# Sheet1.net
KiCad netlist of a schematic drawn in Altium Designer
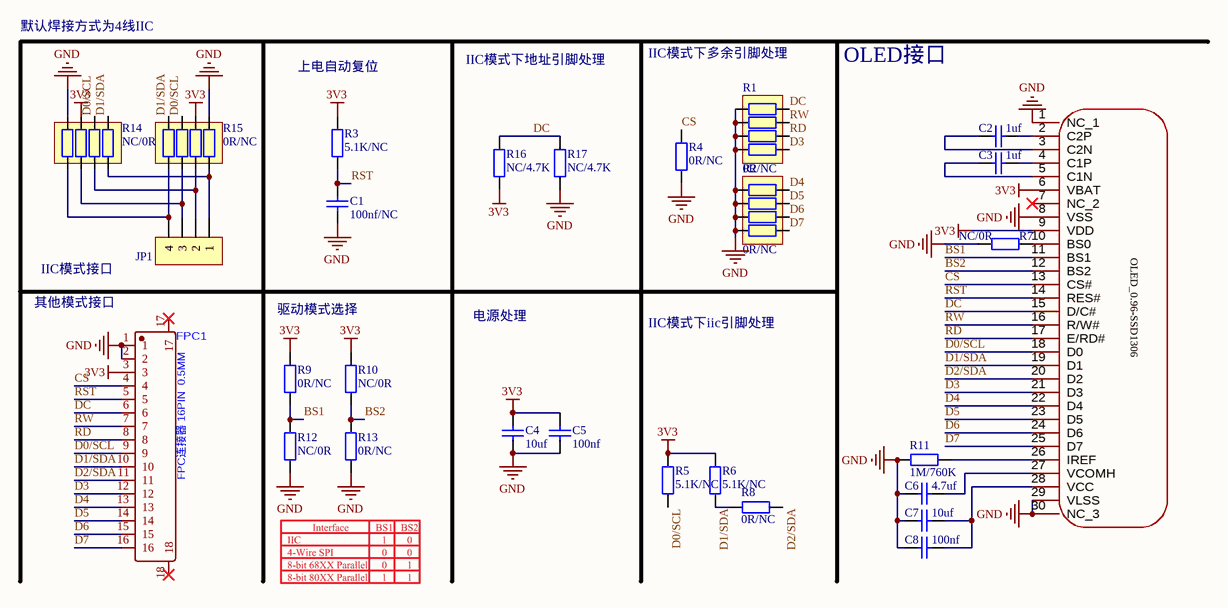
[diagram p0: Sheet1.SchDoc]

(export (version "E")
  (design (tool "Eeschema 10.0.6"))
  (components
    (comp (ref "C1")
      (value "100nf/NC")
      (footprint "PCB1:C0402_L")
      (description "贴片电容/MLCC电容")
      (libsource (lib "0.96_OLED_screen") (part "C"))
    )
    (comp (ref "C2")
      (value "1uf")
      (footprint "PCB1:C0402_L")
      (description "贴片电容/MLCC电容")
      (libsource (lib "0.96_OLED_screen") (part "C"))
    )
    (comp (ref "C3")
      (value "1uf")
      (footprint "PCB1:C0402_L")
      (description "贴片电容/MLCC电容")
      (libsource (lib "0.96_OLED_screen") (part "C"))
    )
    (comp (ref "C4")
      (value "10uf")
      (footprint "PCB1:C0402_L")
      (description "贴片电容/MLCC电容")
      (libsource (lib "0.96_OLED_screen") (part "C"))
    )
    (comp (ref "C5")
      (value "100nf")
      (footprint "PCB1:C0402_L")
      (description "贴片电容/MLCC电容")
      (libsource (lib "0.96_OLED_screen") (part "C"))
    )
    (comp (ref "C6")
      (value "4.7uf")
      (footprint "PCB1:C0402_L")
      (description "贴片电容/MLCC电容")
      (libsource (lib "0.96_OLED_screen") (part "C"))
    )
    (comp (ref "C7")
      (value "10uf")
      (footprint "PCB1:C0402_L")
      (description "贴片电容/MLCC电容")
      (libsource (lib "0.96_OLED_screen") (part "C"))
    )
    (comp (ref "C8")
      (value "100nf")
      (footprint "PCB1:C0402_L")
      (description "贴片电容/MLCC电容")
      (libsource (lib "0.96_OLED_screen") (part "C"))
    )
    (comp (ref "FPC1")
      (value "FPC连接器 16PIN  0.5MM")
      (footprint "PCB1:FPC-SMD_FPC-0.5MM-16P")
      (libsource (lib "0.96_OLED_screen") (part "FPC连接器 16PIN  0.5MM"))
    )
    (comp (ref "JP1")
      (value "HDR-1X4")
      (footprint "PCB1:HDR2.54-LI-4P")
      (description "4P接插件")
      (libsource (lib "0.96_OLED_screen") (part "Header 4"))
    )
    (comp (ref "R1")
      (value "0R/NC")
      (footprint "PCB1:RCA-8P4R-0402")
      (description "贴片4P排阻")
      (libsource (lib "") (part "R-8P4R_1"))
    )
    (comp (ref "R2")
      (value "0R/NC")
      (footprint "PCB1:RCA-8P4R-0402")
      (description "贴片4P排阻")
      (libsource (lib "") (part "R-8P4R_1"))
    )
    (comp (ref "R3")
      (value "5.1K/NC")
      (footprint "PCB1:R0402_L")
      (description "贴片电阻")
      (libsource (lib "0.96_OLED_screen") (part "R"))
    )
    (comp (ref "R4")
      (value "0R/NC")
      (footprint "PCB1:R0402_L")
      (description "贴片电阻")
      (libsource (lib "0.96_OLED_screen") (part "R"))
    )
    (comp (ref "R5")
      (value "5.1K/NC")
      (footprint "PCB1:R0402_L")
      (description "贴片电阻")
      (libsource (lib "0.96_OLED_screen") (part "R"))
    )
    (comp (ref "R6")
      (value "5.1K/NC")
      (footprint "PCB1:R0402_L")
      (description "贴片电阻")
      (libsource (lib "0.96_OLED_screen") (part "R"))
    )
    (comp (ref "R7")
      (value "NC/0R")
      (footprint "PCB1:R0402_L")
      (description "贴片电阻")
      (libsource (lib "0.96_OLED_screen") (part "R"))
    )
    (comp (ref "R8")
      (value "0R/NC")
      (footprint "PCB1:R0402_L")
      (description "贴片电阻")
      (libsource (lib "0.96_OLED_screen") (part "R"))
    )
    (comp (ref "R9")
      (value "0R/NC")
      (footprint "PCB1:R0402_L")
      (description "贴片电阻")
      (libsource (lib "0.96_OLED_screen") (part "R"))
    )
    (comp (ref "R10")
      (value "NC/0R")
      (footprint "PCB1:R0402_L")
      (description "贴片电阻")
      (libsource (lib "0.96_OLED_screen") (part "R"))
    )
    (comp (ref "R11")
      (value "1M/760K")
      (footprint "PCB1:R0402_L")
      (description "贴片电阻")
      (libsource (lib "0.96_OLED_screen") (part "R"))
    )
    (comp (ref "R12")
      (value "NC/0R")
      (footprint "PCB1:R0402_L")
      (description "贴片电阻")
      (libsource (lib "0.96_OLED_screen") (part "R"))
    )
    (comp (ref "R13")
      (value "0R/NC")
      (footprint "PCB1:R0402_L")
      (description "贴片电阻")
      (libsource (lib "0.96_OLED_screen") (part "R"))
    )
    (comp (ref "R14")
      (value "NC/0R")
      (footprint "PCB1:RCA-8P4R-0402")
      (description "贴片电阻")
      (libsource (lib "0.96_OLED_screen") (part "R-8P4R"))
    )
    (comp (ref "R15")
      (value "0R/NC")
      (footprint "PCB1:RCA-8P4R-0402")
      (description "贴片4P排阻")
      (libsource (lib "0.96_OLED_screen") (part "R-8P4R"))
    )
    (comp (ref "R16")
      (value "NC/4.7K")
      (footprint "PCB1:R0402_L")
      (description "贴片电阻")
      (libsource (lib "0.96_OLED_screen") (part "R"))
    )
    (comp (ref "R17")
      (value "NC/4.7K")
      (footprint "PCB1:R0402_L")
      (description "贴片电阻")
      (libsource (lib "0.96_OLED_screen") (part "R"))
    )
    (comp (ref "U1")
      (value "SSD1306")
      (footprint "PCB1:1.3OLED-2")
      (libsource (lib "0.96_OLED_screen") (part "SSD1306"))
    )
  )
  (nets
    (net (code "1") (name "/BS1") (class "Default")
      (node (ref "R12") (pin "2") (pinfunction "2_2") (pintype "passive"))
      (node (ref "R9") (pin "1") (pinfunction "1_1") (pintype "passive"))
      (node (ref "U1") (pin "11") (pinfunction "BS1_11") (pintype "passive"))
    )
    (net (code "2") (name "/BS2") (class "Default")
      (node (ref "R10") (pin "1") (pinfunction "1_1") (pintype "passive"))
      (node (ref "R13") (pin "2") (pinfunction "2_2") (pintype "passive"))
      (node (ref "U1") (pin "12") (pinfunction "BS2_12") (pintype "passive"))
    )
    (net (code "3") (name "/CS") (class "Default")
      (node (ref "FPC1") (pin "4") (pinfunction "4_4") (pintype "passive"))
      (node (ref "R4") (pin "1") (pinfunction "1_1") (pintype "passive"))
      (node (ref "U1") (pin "13") (pinfunction "CS#_13") (pintype "passive"))
    )
    (net (code "4") (name "/D0{slash}SCL") (class "Default")
      (node (ref "FPC1") (pin "9") (pinfunction "9_9") (pintype "passive"))
      (node (ref "R14") (pin "6") (pinfunction "6_6") (pintype "passive"))
      (node (ref "R15") (pin "7") (pinfunction "7_7") (pintype "passive"))
      (node (ref "R5") (pin "1") (pinfunction "1_1") (pintype "passive"))
      (node (ref "U1") (pin "18") (pinfunction "D0_18") (pintype "passive"))
    )
    (net (code "5") (name "/D1{slash}SDA") (class "Default")
      (node (ref "FPC1") (pin "10") (pinfunction "10_10") (pintype "passive"))
      (node (ref "R14") (pin "5") (pinfunction "5_5") (pintype "passive"))
      (node (ref "R15") (pin "8") (pinfunction "8_8") (pintype "passive"))
      (node (ref "R6") (pin "1") (pinfunction "1_1") (pintype "passive"))
      (node (ref "R8") (pin "2") (pinfunction "2_2") (pintype "passive"))
      (node (ref "U1") (pin "19") (pinfunction "D1_19") (pintype "passive"))
    )
    (net (code "6") (name "/D2{slash}SDA") (class "Default")
      (node (ref "FPC1") (pin "11") (pinfunction "11_11") (pintype "passive"))
      (node (ref "R8") (pin "1") (pinfunction "1_1") (pintype "passive"))
      (node (ref "U1") (pin "20") (pinfunction "D2_20") (pintype "passive"))
    )
    (net (code "7") (name "/D3") (class "Default")
      (node (ref "FPC1") (pin "12") (pinfunction "12_12") (pintype "passive"))
      (node (ref "R1") (pin "5") (pinfunction "5_5") (pintype "passive"))
      (node (ref "U1") (pin "21") (pinfunction "D3_21") (pintype "passive"))
    )
    (net (code "8") (name "/D4") (class "Default")
      (node (ref "FPC1") (pin "13") (pinfunction "13_13") (pintype "passive"))
      (node (ref "R2") (pin "8") (pinfunction "8_8") (pintype "passive"))
      (node (ref "U1") (pin "22") (pinfunction "D4_22") (pintype "passive"))
    )
    (net (code "9") (name "/D5") (class "Default")
      (node (ref "FPC1") (pin "14") (pinfunction "14_14") (pintype "passive"))
      (node (ref "R2") (pin "7") (pinfunction "7_7") (pintype "passive"))
      (node (ref "U1") (pin "23") (pinfunction "D5_23") (pintype "passive"))
    )
    (net (code "10") (name "/D6") (class "Default")
      (node (ref "FPC1") (pin "15") (pinfunction "15_15") (pintype "passive"))
      (node (ref "R2") (pin "6") (pinfunction "6_6") (pintype "passive"))
      (node (ref "U1") (pin "24") (pinfunction "D6_24") (pintype "passive"))
    )
    (net (code "11") (name "/D7") (class "Default")
      (node (ref "FPC1") (pin "16") (pinfunction "16_16") (pintype "passive"))
      (node (ref "R2") (pin "5") (pinfunction "5_5") (pintype "passive"))
      (node (ref "U1") (pin "25") (pinfunction "D7_25") (pintype "passive"))
    )
    (net (code "12") (name "/DC") (class "Default")
      (node (ref "FPC1") (pin "6") (pinfunction "6_6") (pintype "passive"))
      (node (ref "R1") (pin "8") (pinfunction "8_8") (pintype "passive"))
      (node (ref "R16") (pin "1") (pinfunction "1_1") (pintype "passive"))
      (node (ref "R17") (pin "1") (pinfunction "1_1") (pintype "passive"))
      (node (ref "U1") (pin "15") (pinfunction "D/C#_15") (pintype "passive"))
    )
    (net (code "13") (name "/RD") (class "Default")
      (node (ref "FPC1") (pin "8") (pinfunction "8_8") (pintype "passive"))
      (node (ref "R1") (pin "6") (pinfunction "6_6") (pintype "passive"))
      (node (ref "U1") (pin "17") (pinfunction "E/RD#_17") (pintype "passive"))
    )
    (net (code "14") (name "/RST") (class "Default")
      (node (ref "C1") (pin "2") (pinfunction "2_2") (pintype "passive"))
      (node (ref "FPC1") (pin "5") (pinfunction "5_5") (pintype "passive"))
      (node (ref "R3") (pin "2") (pinfunction "2_2") (pintype "passive"))
      (node (ref "U1") (pin "14") (pinfunction "RES#_14") (pintype "passive"))
    )
    (net (code "15") (name "/RW") (class "Default")
      (node (ref "FPC1") (pin "7") (pinfunction "7_7") (pintype "passive"))
      (node (ref "R1") (pin "7") (pinfunction "7_7") (pintype "passive"))
      (node (ref "U1") (pin "16") (pinfunction "R/W#_16") (pintype "passive"))
    )
    (net (code "16") (name "3V3") (class "Default")
      (node (ref "C4") (pin "2") (pinfunction "2_2") (pintype "passive"))
      (node (ref "C5") (pin "2") (pinfunction "2_2") (pintype "passive"))
      (node (ref "FPC1") (pin "3") (pinfunction "3_3") (pintype "passive"))
      (node (ref "R10") (pin "2") (pinfunction "2_2") (pintype "passive"))
      (node (ref "R14") (pin "7") (pinfunction "7_7") (pintype "passive"))
      (node (ref "R15") (pin "6") (pinfunction "6_6") (pintype "passive"))
      (node (ref "R16") (pin "2") (pinfunction "2_2") (pintype "passive"))
      (node (ref "R3") (pin "1") (pinfunction "1_1") (pintype "passive"))
      (node (ref "R5") (pin "2") (pinfunction "2_2") (pintype "passive"))
      (node (ref "R6") (pin "2") (pinfunction "2_2") (pintype "passive"))
      (node (ref "R9") (pin "2") (pinfunction "2_2") (pintype "passive"))
      (node (ref "U1") (pin "6") (pinfunction "VBAT_6") (pintype "passive"))
      (node (ref "U1") (pin "9") (pinfunction "VDD_9") (pintype "passive"))
    )
    (net (code "17") (name "GND") (class "Default")
      (node (ref "C1") (pin "1") (pinfunction "1_1") (pintype "passive"))
      (node (ref "C4") (pin "1") (pinfunction "1_1") (pintype "passive"))
      (node (ref "C5") (pin "1") (pinfunction "1_1") (pintype "passive"))
      (node (ref "C6") (pin "1") (pinfunction "1_1") (pintype "passive"))
      (node (ref "C7") (pin "1") (pinfunction "1_1") (pintype "passive"))
      (node (ref "C8") (pin "1") (pinfunction "1_1") (pintype "passive"))
      (node (ref "FPC1") (pin "1") (pinfunction "1_1") (pintype "passive"))
      (node (ref "FPC1") (pin "2") (pinfunction "2_2") (pintype "passive"))
      (node (ref "R1") (pin "1") (pinfunction "1_1") (pintype "passive"))
      (node (ref "R1") (pin "2") (pinfunction "2_2") (pintype "passive"))
      (node (ref "R1") (pin "3") (pinfunction "3_3") (pintype "passive"))
      (node (ref "R1") (pin "4") (pinfunction "4_4") (pintype "passive"))
      (node (ref "R11") (pin "1") (pinfunction "1_1") (pintype "passive"))
      (node (ref "R12") (pin "1") (pinfunction "1_1") (pintype "passive"))
      (node (ref "R13") (pin "1") (pinfunction "1_1") (pintype "passive"))
      (node (ref "R14") (pin "8") (pinfunction "8_8") (pintype "passive"))
      (node (ref "R15") (pin "5") (pinfunction "5_5") (pintype "passive"))
      (node (ref "R17") (pin "2") (pinfunction "2_2") (pintype "passive"))
      (node (ref "R2") (pin "1") (pinfunction "1_1") (pintype "passive"))
      (node (ref "R2") (pin "2") (pinfunction "2_2") (pintype "passive"))
      (node (ref "R2") (pin "3") (pinfunction "3_3") (pintype "passive"))
      (node (ref "R2") (pin "4") (pinfunction "4_4") (pintype "passive"))
      (node (ref "R4") (pin "2") (pinfunction "2_2") (pintype "passive"))
      (node (ref "R7") (pin "2") (pinfunction "2_2") (pintype "passive"))
      (node (ref "U1") (pin "1") (pinfunction "NC_1_1") (pintype "passive"))
      (node (ref "U1") (pin "29") (pinfunction "VLSS_29") (pintype "passive"))
      (node (ref "U1") (pin "30") (pinfunction "NC_3_30") (pintype "passive"))
      (node (ref "U1") (pin "8") (pinfunction "VSS_8") (pintype "passive"))
    )
    (net (code "18") (name "Net-(JP1-Pad1)") (class "Default")
      (node (ref "JP1") (pin "1") (pinfunction "1_1") (pintype "passive"))
      (node (ref "R14") (pin "4") (pinfunction "4_4") (pintype "passive"))
      (node (ref "R15") (pin "4") (pinfunction "4_4") (pintype "passive"))
    )
    (net (code "19") (name "Net-(JP1-Pad2)") (class "Default")
      (node (ref "JP1") (pin "2") (pinfunction "2_2") (pintype "passive"))
      (node (ref "R14") (pin "3") (pinfunction "3_3") (pintype "passive"))
      (node (ref "R15") (pin "3") (pinfunction "3_3") (pintype "passive"))
    )
    (net (code "20") (name "Net-(JP1-Pad3)") (class "Default")
      (node (ref "JP1") (pin "3") (pinfunction "3_3") (pintype "passive"))
      (node (ref "R14") (pin "2") (pinfunction "2_2") (pintype "passive"))
      (node (ref "R15") (pin "2") (pinfunction "2_2") (pintype "passive"))
    )
    (net (code "21") (name "Net-(JP1-Pad4)") (class "Default")
      (node (ref "JP1") (pin "4") (pinfunction "4_4") (pintype "passive"))
      (node (ref "R14") (pin "1") (pinfunction "1_1") (pintype "passive"))
      (node (ref "R15") (pin "1") (pinfunction "1_1") (pintype "passive"))
    )
    (net (code "22") (name "Net-(U1-BS0)") (class "Default")
      (node (ref "R7") (pin "1") (pinfunction "1_1") (pintype "passive"))
      (node (ref "U1") (pin "10") (pinfunction "BS0_10") (pintype "passive"))
    )
    (net (code "23") (name "Net-(U1-C1N)") (class "Default")
      (node (ref "C3") (pin "1") (pinfunction "1_1") (pintype "passive"))
      (node (ref "U1") (pin "5") (pinfunction "C1N_5") (pintype "passive"))
    )
    (net (code "24") (name "Net-(U1-C1P)") (class "Default")
      (node (ref "C3") (pin "2") (pinfunction "2_2") (pintype "passive"))
      (node (ref "U1") (pin "4") (pinfunction "C1P_4") (pintype "passive"))
    )
    (net (code "25") (name "Net-(U1-C2N)") (class "Default")
      (node (ref "C2") (pin "1") (pinfunction "1_1") (pintype "passive"))
      (node (ref "U1") (pin "3") (pinfunction "C2N_3") (pintype "passive"))
    )
    (net (code "26") (name "Net-(U1-C2P)") (class "Default")
      (node (ref "C2") (pin "2") (pinfunction "2_2") (pintype "passive"))
      (node (ref "U1") (pin "2") (pinfunction "C2P_2") (pintype "passive"))
    )
    (net (code "27") (name "Net-(U1-IREF)") (class "Default")
      (node (ref "R11") (pin "2") (pinfunction "2_2") (pintype "passive"))
      (node (ref "U1") (pin "26") (pinfunction "IREF_26") (pintype "passive"))
    )
    (net (code "28") (name "Net-(U1-VCC)") (class "Default")
      (node (ref "C7") (pin "2") (pinfunction "2_2") (pintype "passive"))
      (node (ref "C8") (pin "2") (pinfunction "2_2") (pintype "passive"))
      (node (ref "U1") (pin "28") (pinfunction "VCC_28") (pintype "passive"))
    )
    (net (code "29") (name "Net-(U1-VCOMH)") (class "Default")
      (node (ref "C6") (pin "2") (pinfunction "2_2") (pintype "passive"))
      (node (ref "U1") (pin "27") (pinfunction "VCOMH_27") (pintype "passive"))
    )
    (net (code "30") (name "unconnected-(FPC1-Pad17)") (class "Default")
      (node (ref "FPC1") (pin "17") (pinfunction "17_17") (pintype "passive+no_connect"))
    )
    (net (code "31") (name "unconnected-(FPC1-Pad18)") (class "Default")
      (node (ref "FPC1") (pin "18") (pinfunction "18_18") (pintype "passive+no_connect"))
    )
    (net (code "32") (name "unconnected-(U1-NC_2-Pad7)") (class "Default")
      (node (ref "U1") (pin "7") (pinfunction "NC_2_7") (pintype "passive+no_connect"))
    )
  )
)
